# SCH_rocket_competetion_2025-11-04.net
KiCad netlist of a schematic drawn in EasyEDA
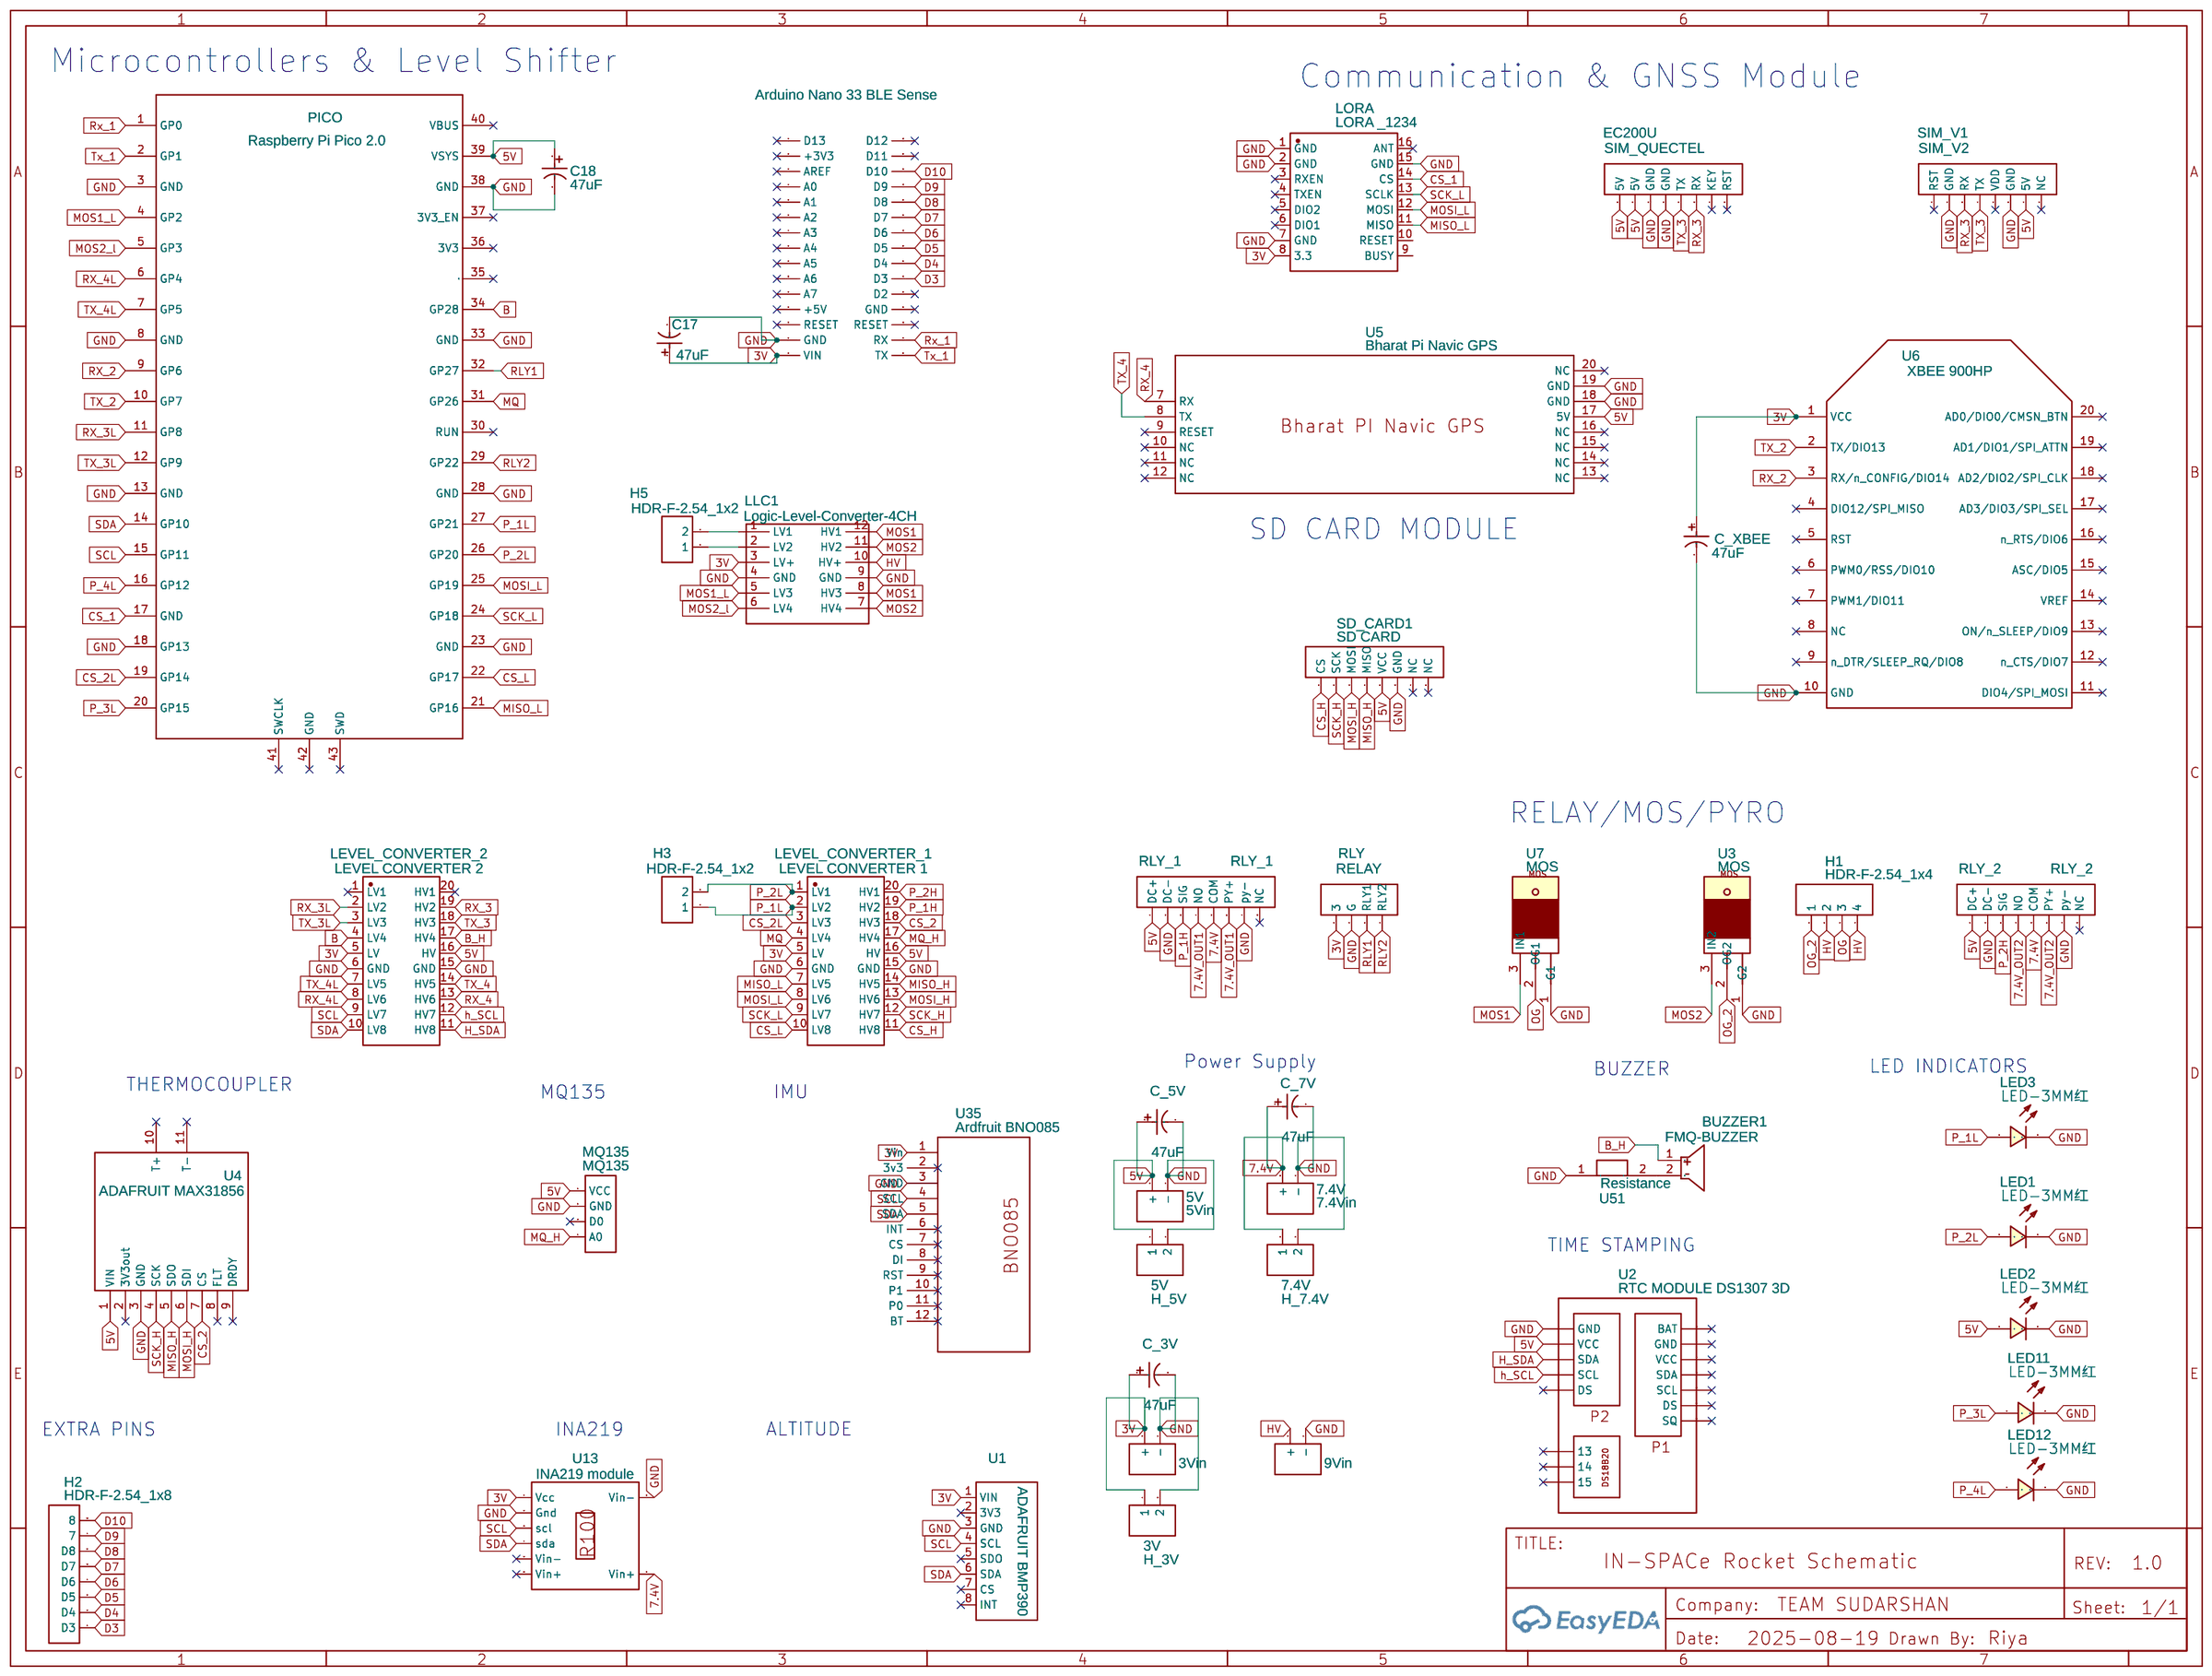
[diagram p0: schematic sheet]

(export (version "E")
  (design (tool "Eeschema 10.0.6"))
  (components
    (comp (ref "3.3V") (value "3Vin") (libsource (lib "") (part "CONN-TH_2P-P5.00")))
    (comp (ref "5V") (value "5Vin") (libsource (lib "") (part "CONN-TH_2P-P5.00_2")))
    (comp (ref "7.4V") (value "7.4Vin") (libsource (lib "") (part "CONN-TH_2P-P5.00_1")))
    (comp (ref "9V") (value "9Vin") (libsource (lib "") (part "CONN-TH_2P-P5.00_3")))
    (comp (ref "BLE33")
      (value "Arduino Nano 33 BLE Sense")
      (libsource (lib "") (part "Arduino Nano 33 BLE Sense"))
    )
    (comp (ref "BUZZER1")
      (value "FMQ-BUZZER")
      (fields (field (name "Manufacturer Part") "FMQ-BUZZER2"))
      (libsource (lib "") (part "FMQ-BUZZER2"))
    )
    (comp (ref "C17")
      (value "47uF")
      (fields
        (field (name "Manufacturer Part") "KM476M016D11RR0VH2FP0")
        (field (name "Manufacturer") "CX(承兴)")
      )
      (libsource (lib "") (part "CAPACITOR COPY_5"))
    )
    (comp (ref "C18")
      (value "47uF")
      (fields
        (field (name "Manufacturer Part") "KM476M016D11RR0VH2FP0")
        (field (name "Manufacturer") "CX(承兴)")
      )
      (libsource (lib "") (part "CAPACITOR COPY_1"))
    )
    (comp (ref "C_3V")
      (value "47uF")
      (fields
        (field (name "Manufacturer Part") "KM476M016D11RR0VH2FP0")
        (field (name "Manufacturer") "CX(承兴)")
      )
      (libsource (lib "") (part "CAPACITOR COPY_3"))
    )
    (comp (ref "C_5V")
      (value "47uF")
      (fields
        (field (name "Manufacturer Part") "KM476M016D11RR0VH2FP0")
        (field (name "Manufacturer") "CX(承兴)")
      )
      (libsource (lib "") (part "CAPACITOR COPY"))
    )
    (comp (ref "C_7V")
      (value "47uF")
      (fields
        (field (name "Manufacturer Part") "KM476M016D11RR0VH2FP0")
        (field (name "Manufacturer") "CX(承兴)")
      )
      (libsource (lib "") (part "CAPACITOR COPY_4"))
    )
    (comp (ref "C_XBEE")
      (value "47uF")
      (fields
        (field (name "Manufacturer Part") "KM476M016D11RR0VH2FP0")
        (field (name "Manufacturer") "CX(承兴)")
      )
      (libsource (lib "") (part "CAPACITOR COPY_2"))
    )
    (comp (ref "EC200U") (value "SIM_QUECTEL") (libsource (lib "") (part "HDR-F-2.54_1x8_3")))
    (comp (ref "H1") (value "HDR-F-2.54_1x4") (libsource (lib "") (part "HDR-F-2.54_1x4")))
    (comp (ref "H2") (value "HDR-F-2.54_1x8") (libsource (lib "") (part "HDR-F-2.54_1x8")))
    (comp (ref "H3") (value "HDR-F-2.54_1x2") (libsource (lib "") (part "HDR-F-2.54_1x2")))
    (comp (ref "H5") (value "HDR-F-2.54_1x2") (libsource (lib "") (part "HDR-F-2.54_1x2")))
    (comp (ref "H_3V") (value "3V") (libsource (lib "") (part "HDR-F-2.54_1x2_3")))
    (comp (ref "H_5V") (value "5V") (libsource (lib "") (part "HDR-F-2.54_1x2_2")))
    (comp (ref "H_7.4V") (value "7.4V") (libsource (lib "") (part "HDR-F-2.54_1x2_1")))
    (comp (ref "LED1")
      (value "LED-3MM红")
      (fields (field (name "Manufacturer Part") "LED-3mm红"))
      (libsource (lib "") (part "LED-3MM红"))
    )
    (comp (ref "LED2")
      (value "LED-3MM红")
      (fields (field (name "Manufacturer Part") "LED-3mm红"))
      (libsource (lib "") (part "LED-3MM红"))
    )
    (comp (ref "LED3")
      (value "LED-3MM红")
      (fields (field (name "Manufacturer Part") "LED-3mm红"))
      (libsource (lib "") (part "LED-3MM红"))
    )
    (comp (ref "LED11")
      (value "LED-3MM红")
      (fields (field (name "Manufacturer Part") "LED-3mm红"))
      (libsource (lib "") (part "LED-3MM红"))
    )
    (comp (ref "LED12")
      (value "LED-3MM红")
      (fields (field (name "Manufacturer Part") "LED-3mm红"))
      (libsource (lib "") (part "LED-3MM红"))
    )
    (comp (ref "LEVEL_CONVERTER_1")
      (value "LEVEL CONVERTER 1")
      (fields (field (name "Manufacturer Part") "Level Converter 8"))
      (libsource (lib "") (part "LEVEL CONVERTER 8"))
    )
    (comp (ref "LEVEL_CONVERTER_2")
      (value "LEVEL CONVERTER 2")
      (fields (field (name "Manufacturer Part") "Level Converter 8"))
      (libsource (lib "") (part "LEVEL CONVERTER 8"))
    )
    (comp (ref "LLC1")
      (value "Logic-Level-Converter-4CH")
      (libsource (lib "") (part "Logic-Level-Converter-4CH"))
    )
    (comp (ref "LORA")
      (value "LORA _1234")
      (fields (field (name "Manufacturer Part") "LORA"))
      (libsource (lib "") (part "LORA _1234"))
    )
    (comp (ref "MQ135") (value "MQ135") (libsource (lib "") (part "HDR-F-2.54_1x4_2")))
    (comp (ref "PICO")
      (value "Raspberry Pi Pico 2.0")
      (fields (field (name "Manufacturer Part") "Raspberry Pi Pico"))
      (libsource (lib "") (part "Raspberry Pi Pico 2.0"))
    )
    (comp (ref "RLY") (value "RELAY") (libsource (lib "") (part "HDR-F-2.54_1x4_1")))
    (comp (ref "RLY_1") (value "RLY_1") (libsource (lib "") (part "HDR-F-2.54_1x8_2")))
    (comp (ref "RLY_2") (value "RLY_2") (libsource (lib "") (part "HDR-F-2.54_1x8_2")))
    (comp (ref "SD_CARD1") (value "SD CARD") (libsource (lib "") (part "HDR-F-2.54_1x8_4")))
    (comp (ref "SIM_V1") (value "SIM_V2") (libsource (lib "") (part "HDR-F-2.54_1x8_1")))
    (comp (ref "U1")
      (value "ADAFRUIT BMP390")
      (fields (field (name "Manufacturer Part") "ADAFRUIT"))
      (libsource (lib "") (part "ADAFRUIT BMP390 COPY"))
    )
    (comp (ref "U2") (value "RTC MODULE DS1307 3D") (libsource (lib "") (part "RTC MODULE DS1307 3D")))
    (comp (ref "U3") (value "MOS") (libsource (lib "") (part "MOS")))
    (comp (ref "U4")
      (value "ADAFRUIT MAX31856")
      (fields (field (name "Manufacturer Part") "ADAFRUIT"))
      (libsource (lib "") (part "ADAFRUIT MAX31856"))
    )
    (comp (ref "U5") (value "Bharat Pi Navic GPS") (libsource (lib "") (part "Bharat Pi Navic GPS")))
    (comp (ref "U6")
      (value "XBEE 900HP")
      (fields
        (field (name "Manufacturer Part") "XBP24CZ7PITB003")
        (field (name "Manufacturer") "Digi International")
      )
      (libsource (lib "") (part "XBEE_THT"))
    )
    (comp (ref "U7") (value "MOS") (libsource (lib "") (part "MOS_1")))
    (comp (ref "U13")
      (value "INA219 module")
      (fields (field (name "Manufacturer Part") "INA219") (field (name "Manufacturer") "TI"))
      (libsource (lib "") (part "INA219 module"))
    )
    (comp (ref "U35")
      (value "Ardfruit BNO085")
      (fields (field (name "Manufacturer") "Ardfruit"))
      (libsource (lib "") (part "Ardfruit BNO085"))
    )
    (comp (ref "U51") (value "Resistance") (libsource (lib "") (part "Resistance")))
  )
  (nets
    (net (code "1") (name "3V") (class "Default")
      (node (ref "3.3V") (pin "2") (pinfunction "+_2") (pintype "unspecified"))
      (node (ref "BLE33") (pin "15") (pinfunction "VIN_15") (pintype "unspecified"))
      (node (ref "C17") (pin "1") (pinfunction "1_1") (pintype "unspecified"))
      (node (ref "C_3V") (pin "1") (pinfunction "1_1") (pintype "unspecified"))
      (node (ref "C_XBEE") (pin "1") (pinfunction "1_1") (pintype "unspecified"))
      (node (ref "H_3V") (pin "1") (pinfunction "1_1") (pintype "input"))
      (node (ref "LEVEL_CONVERTER_1") (pin "5") (pinfunction "LV_5") (pintype "unspecified"))
      (node (ref "LEVEL_CONVERTER_2") (pin "5") (pinfunction "LV_5") (pintype "unspecified"))
      (node (ref "LLC1") (pin "3") (pinfunction "LV+_3") (pintype "unspecified"))
      (node (ref "LORA") (pin "8") (pinfunction "3.3_8") (pintype "unspecified"))
      (node (ref "RLY") (pin "1") (pinfunction "3_1") (pintype "unspecified"))
      (node (ref "U1") (pin "1") (pinfunction "VIN_1") (pintype "unspecified"))
      (node (ref "U13") (pin "1") (pinfunction "Vcc_1") (pintype "input"))
      (node (ref "U35") (pin "1") (pinfunction "Vin_1") (pintype "unspecified"))
      (node (ref "U6") (pin "1") (pinfunction "VCC_1") (pintype "passive"))
    )
    (net (code "2") (name "5V") (class "Default")
      (node (ref "5V") (pin "2") (pinfunction "+_2") (pintype "unspecified"))
      (node (ref "C18") (pin "1") (pinfunction "1_1") (pintype "unspecified"))
      (node (ref "C_5V") (pin "1") (pinfunction "1_1") (pintype "unspecified"))
      (node (ref "EC200U") (pin "1") (pinfunction "5V_1") (pintype "unspecified"))
      (node (ref "EC200U") (pin "2") (pinfunction "5V_2") (pintype "unspecified"))
      (node (ref "H_5V") (pin "1") (pinfunction "1_1") (pintype "input"))
      (node (ref "LED2") (pin "1") (pinfunction "1_1") (pintype "unspecified"))
      (node (ref "LEVEL_CONVERTER_1") (pin "16") (pinfunction "HV_16") (pintype "unspecified"))
      (node (ref "LEVEL_CONVERTER_2") (pin "16") (pinfunction "HV_16") (pintype "unspecified"))
      (node (ref "MQ135") (pin "1") (pinfunction "VCC_1") (pintype "unspecified"))
      (node (ref "PICO") (pin "39") (pinfunction "VSYS_39") (pintype "unspecified"))
      (node (ref "RLY_1") (pin "1") (pinfunction "DC+_1") (pintype "unspecified"))
      (node (ref "RLY_2") (pin "1") (pinfunction "DC+_1") (pintype "unspecified"))
      (node (ref "SD_CARD1") (pin "5") (pinfunction "VCC_5") (pintype "unspecified"))
      (node (ref "SIM_V1") (pin "7") (pinfunction "5V_7") (pintype "unspecified"))
      (node (ref "U2") (pin "2") (pinfunction "VCC_2") (pintype "unspecified"))
      (node (ref "U4") (pin "1") (pinfunction "VIN_1") (pintype "unspecified"))
      (node (ref "U5") (pin "17") (pinfunction "5V_17") (pintype "unspecified"))
    )
    (net (code "3") (name "7.4V") (class "Default")
      (node (ref "7.4V") (pin "2") (pinfunction "+_2") (pintype "unspecified"))
      (node (ref "C_7V") (pin "1") (pinfunction "1_1") (pintype "unspecified"))
      (node (ref "H_7.4V") (pin "1") (pinfunction "1_1") (pintype "input"))
      (node (ref "RLY_1") (pin "5") (pinfunction "COM_5") (pintype "unspecified"))
      (node (ref "RLY_2") (pin "5") (pinfunction "COM_5") (pintype "unspecified"))
      (node (ref "U13") (pin "6") (pinfunction "Vin+_6") (pintype "input"))
    )
    (net (code "4") (name "7.4V_OUT1") (class "Default")
      (node (ref "RLY_1") (pin "4") (pinfunction "NO_4") (pintype "unspecified"))
      (node (ref "RLY_1") (pin "6") (pinfunction "PY+_6") (pintype "unspecified"))
    )
    (net (code "5") (name "7.4V_OUT2") (class "Default")
      (node (ref "RLY_2") (pin "4") (pinfunction "NO_4") (pintype "unspecified"))
      (node (ref "RLY_2") (pin "6") (pinfunction "PY+_6") (pintype "unspecified"))
    )
    (net (code "6") (name "B") (class "Default")
      (node (ref "LEVEL_CONVERTER_2") (pin "4") (pinfunction "LV4_4") (pintype "unspecified"))
      (node (ref "PICO") (pin "34") (pinfunction "GP28_34") (pintype "unspecified"))
    )
    (net (code "7") (name "B_H") (class "Default")
      (node (ref "BUZZER1") (pin "1") (pinfunction "1_1") (pintype "unspecified"))
      (node (ref "LEVEL_CONVERTER_2") (pin "17") (pinfunction "HV4_17") (pintype "unspecified"))
    )
    (net (code "8") (name "CS_1") (class "Default")
      (node (ref "LORA") (pin "14") (pinfunction "CS_14") (pintype "unspecified"))
      (node (ref "PICO") (pin "17") (pinfunction "GND_17") (pintype "unspecified"))
    )
    (net (code "9") (name "CS_2") (class "Default")
      (node (ref "LEVEL_CONVERTER_1") (pin "18") (pinfunction "HV3_18") (pintype "unspecified"))
      (node (ref "U4") (pin "7") (pinfunction "CS_7") (pintype "unspecified"))
    )
    (net (code "10") (name "CS_2L") (class "Default")
      (node (ref "LEVEL_CONVERTER_1") (pin "3") (pinfunction "LV3_3") (pintype "unspecified"))
      (node (ref "PICO") (pin "19") (pinfunction "GP14_19") (pintype "unspecified"))
    )
    (net (code "11") (name "CS_H") (class "Default")
      (node (ref "LEVEL_CONVERTER_1") (pin "11") (pinfunction "HV8_11") (pintype "unspecified"))
      (node (ref "SD_CARD1") (pin "1") (pinfunction "CS_1") (pintype "unspecified"))
    )
    (net (code "12") (name "CS_L") (class "Default")
      (node (ref "LEVEL_CONVERTER_1") (pin "10") (pinfunction "LV8_10") (pintype "unspecified"))
      (node (ref "PICO") (pin "22") (pinfunction "GP17_22") (pintype "unspecified"))
    )
    (net (code "13") (name "D3") (class "Default")
      (node (ref "BLE33") (pin "21") (pinfunction "D3_21") (pintype "unspecified"))
      (node (ref "H2") (pin "1") (pinfunction "D3_1") (pintype "unspecified"))
    )
    (net (code "14") (name "D4") (class "Default")
      (node (ref "BLE33") (pin "22") (pinfunction "D4_22") (pintype "unspecified"))
      (node (ref "H2") (pin "2") (pinfunction "D4_2") (pintype "unspecified"))
    )
    (net (code "15") (name "D5") (class "Default")
      (node (ref "BLE33") (pin "23") (pinfunction "D5_23") (pintype "unspecified"))
      (node (ref "H2") (pin "3") (pinfunction "D5_3") (pintype "unspecified"))
    )
    (net (code "16") (name "D6") (class "Default")
      (node (ref "BLE33") (pin "24") (pinfunction "D6_24") (pintype "unspecified"))
      (node (ref "H2") (pin "4") (pinfunction "D6_4") (pintype "unspecified"))
    )
    (net (code "17") (name "D7") (class "Default")
      (node (ref "BLE33") (pin "25") (pinfunction "D7_25") (pintype "unspecified"))
      (node (ref "H2") (pin "5") (pinfunction "D7_5") (pintype "unspecified"))
    )
    (net (code "18") (name "D8") (class "Default")
      (node (ref "BLE33") (pin "26") (pinfunction "D8_26") (pintype "unspecified"))
      (node (ref "H2") (pin "6") (pinfunction "D8_6") (pintype "unspecified"))
    )
    (net (code "19") (name "D9") (class "Default")
      (node (ref "BLE33") (pin "27") (pinfunction "D9_27") (pintype "unspecified"))
      (node (ref "H2") (pin "7") (pinfunction "7_7") (pintype "unspecified"))
    )
    (net (code "20") (name "D10") (class "Default")
      (node (ref "BLE33") (pin "28") (pinfunction "D10_28") (pintype "unspecified"))
      (node (ref "H2") (pin "8") (pinfunction "8_8") (pintype "unspecified"))
    )
    (net (code "21") (name "GND") (class "Default")
      (node (ref "3.3V") (pin "1") (pinfunction "-_1") (pintype "unspecified"))
      (node (ref "5V") (pin "1") (pinfunction "-_1") (pintype "unspecified"))
      (node (ref "7.4V") (pin "1") (pinfunction "-_1") (pintype "unspecified"))
      (node (ref "9V") (pin "1") (pinfunction "-_1") (pintype "unspecified"))
      (node (ref "BLE33") (pin "14") (pinfunction "GND_14") (pintype "unspecified"))
      (node (ref "C17") (pin "2") (pinfunction "2_2") (pintype "unspecified"))
      (node (ref "C18") (pin "2") (pinfunction "2_2") (pintype "unspecified"))
      (node (ref "C_3V") (pin "2") (pinfunction "2_2") (pintype "unspecified"))
      (node (ref "C_5V") (pin "2") (pinfunction "2_2") (pintype "unspecified"))
      (node (ref "C_7V") (pin "2") (pinfunction "2_2") (pintype "unspecified"))
      (node (ref "C_XBEE") (pin "2") (pinfunction "2_2") (pintype "unspecified"))
      (node (ref "EC200U") (pin "3") (pinfunction "GND_3") (pintype "unspecified"))
      (node (ref "EC200U") (pin "4") (pinfunction "GND_4") (pintype "unspecified"))
      (node (ref "H_3V") (pin "2") (pinfunction "2_2") (pintype "input"))
      (node (ref "H_5V") (pin "2") (pinfunction "2_2") (pintype "input"))
      (node (ref "H_7.4V") (pin "2") (pinfunction "2_2") (pintype "input"))
      (node (ref "LED1") (pin "2") (pinfunction "2_2") (pintype "unspecified"))
      (node (ref "LED11") (pin "2") (pinfunction "2_2") (pintype "unspecified"))
      (node (ref "LED12") (pin "2") (pinfunction "2_2") (pintype "unspecified"))
      (node (ref "LED2") (pin "2") (pinfunction "2_2") (pintype "unspecified"))
      (node (ref "LED3") (pin "2") (pinfunction "2_2") (pintype "unspecified"))
      (node (ref "LEVEL_CONVERTER_1") (pin "15") (pinfunction "GND_15") (pintype "unspecified"))
      (node (ref "LEVEL_CONVERTER_1") (pin "6") (pinfunction "GND_6") (pintype "unspecified"))
      (node (ref "LEVEL_CONVERTER_2") (pin "15") (pinfunction "GND_15") (pintype "unspecified"))
      (node (ref "LEVEL_CONVERTER_2") (pin "6") (pinfunction "GND_6") (pintype "unspecified"))
      (node (ref "LLC1") (pin "4") (pinfunction "GND_4") (pintype "unspecified"))
      (node (ref "LLC1") (pin "9") (pinfunction "GND_9") (pintype "unspecified"))
      (node (ref "LORA") (pin "1") (pinfunction "GND_1") (pintype "unspecified"))
      (node (ref "LORA") (pin "15") (pinfunction "GND_15") (pintype "unspecified"))
      (node (ref "LORA") (pin "2") (pinfunction "GND_2") (pintype "unspecified"))
      (node (ref "LORA") (pin "7") (pinfunction "GND_7") (pintype "unspecified"))
      (node (ref "MQ135") (pin "2") (pinfunction "GND_2") (pintype "unspecified"))
      (node (ref "PICO") (pin "13") (pinfunction "GND_13") (pintype "unspecified"))
      (node (ref "PICO") (pin "18") (pinfunction "GP13_18") (pintype "unspecified"))
      (node (ref "PICO") (pin "23") (pinfunction "GND_23") (pintype "unspecified"))
      (node (ref "PICO") (pin "28") (pinfunction "GND_28") (pintype "unspecified"))
      (node (ref "PICO") (pin "3") (pinfunction "GND_3") (pintype "unspecified"))
      (node (ref "PICO") (pin "33") (pinfunction "GND_33") (pintype "unspecified"))
      (node (ref "PICO") (pin "38") (pinfunction "GND_38") (pintype "unspecified"))
      (node (ref "PICO") (pin "8") (pinfunction "GND_8") (pintype "unspecified"))
      (node (ref "RLY") (pin "2") (pinfunction "G_2") (pintype "unspecified"))
      (node (ref "RLY_1") (pin "2") (pinfunction "DC-_2") (pintype "unspecified"))
      (node (ref "RLY_1") (pin "7") (pinfunction "py-_7") (pintype "unspecified"))
      (node (ref "RLY_2") (pin "2") (pinfunction "DC-_2") (pintype "unspecified"))
      (node (ref "RLY_2") (pin "7") (pinfunction "py-_7") (pintype "unspecified"))
      (node (ref "SD_CARD1") (pin "6") (pinfunction "GND_6") (pintype "unspecified"))
      (node (ref "SIM_V1") (pin "2") (pinfunction "GND_2") (pintype "unspecified"))
      (node (ref "SIM_V1") (pin "6") (pinfunction "GND_6") (pintype "unspecified"))
      (node (ref "U1") (pin "3") (pinfunction "GND_3") (pintype "unspecified"))
      (node (ref "U13") (pin "2") (pinfunction "Gnd_2") (pintype "input"))
      (node (ref "U13") (pin "5") (pinfunction "Vin-_5") (pintype "input"))
      (node (ref "U2") (pin "1") (pinfunction "GND_1") (pintype "unspecified"))
      (node (ref "U3") (pin "1") (pinfunction "G2_1") (pintype "unspecified"))
      (node (ref "U35") (pin "3") (pinfunction "GND_3") (pintype "unspecified"))
      (node (ref "U4") (pin "3") (pinfunction "GND_3") (pintype "unspecified"))
      (node (ref "U5") (pin "18") (pinfunction "GND_18") (pintype "unspecified"))
      (node (ref "U5") (pin "19") (pinfunction "GND_19") (pintype "unspecified"))
      (node (ref "U51") (pin "1") (pinfunction "1_1") (pintype "unspecified"))
      (node (ref "U6") (pin "10") (pinfunction "GND_10") (pintype "passive"))
      (node (ref "U7") (pin "1") (pinfunction "G1_1") (pintype "unspecified"))
    )
    (net (code "22") (name "HV") (class "Default")
      (node (ref "9V") (pin "2") (pinfunction "+_2") (pintype "unspecified"))
      (node (ref "H1") (pin "2") (pinfunction "2_2") (pintype "unspecified"))
      (node (ref "H1") (pin "4") (pinfunction "4_4") (pintype "unspecified"))
      (node (ref "LLC1") (pin "10") (pinfunction "HV+_10") (pintype "unspecified"))
    )
    (net (code "23") (name "H_SDA") (class "Default")
      (node (ref "LEVEL_CONVERTER_2") (pin "11") (pinfunction "HV8_11") (pintype "unspecified"))
      (node (ref "U2") (pin "3") (pinfunction "SDA_3") (pintype "unspecified"))
    )
    (net (code "24") (name "MISO_H") (class "Default")
      (node (ref "LEVEL_CONVERTER_1") (pin "14") (pinfunction "HV5_14") (pintype "unspecified"))
      (node (ref "SD_CARD1") (pin "4") (pinfunction "MISO_4") (pintype "unspecified"))
      (node (ref "U4") (pin "5") (pinfunction "SDO_5") (pintype "unspecified"))
    )
    (net (code "25") (name "MISO_L") (class "Default")
      (node (ref "LEVEL_CONVERTER_1") (pin "7") (pinfunction "LV5_7") (pintype "unspecified"))
      (node (ref "LORA") (pin "11") (pinfunction "MISO_11") (pintype "unspecified"))
      (node (ref "PICO") (pin "21") (pinfunction "GP16_21") (pintype "unspecified"))
    )
    (net (code "26") (name "MOS1") (class "Default")
      (node (ref "LLC1") (pin "12") (pinfunction "HV1_12") (pintype "unspecified"))
      (node (ref "LLC1") (pin "8") (pinfunction "HV3_8") (pintype "unspecified"))
      (node (ref "U7") (pin "3") (pinfunction "IN1_3") (pintype "unspecified"))
    )
    (net (code "27") (name "MOS1_L") (class "Default")
      (node (ref "LLC1") (pin "5") (pinfunction "LV3_5") (pintype "unspecified"))
      (node (ref "PICO") (pin "4") (pinfunction "GP2_4") (pintype "unspecified"))
    )
    (net (code "28") (name "MOS2") (class "Default")
      (node (ref "LLC1") (pin "11") (pinfunction "HV2_11") (pintype "unspecified"))
      (node (ref "LLC1") (pin "7") (pinfunction "HV4_7") (pintype "unspecified"))
      (node (ref "U3") (pin "3") (pinfunction "IN2_3") (pintype "unspecified"))
    )
    (net (code "29") (name "MOS2_l") (class "Default")
      (node (ref "LLC1") (pin "6") (pinfunction "LV4_6") (pintype "unspecified"))
      (node (ref "PICO") (pin "5") (pinfunction "GP3_5") (pintype "unspecified"))
    )
    (net (code "30") (name "MOSI_H") (class "Default")
      (node (ref "LEVEL_CONVERTER_1") (pin "13") (pinfunction "HV6_13") (pintype "unspecified"))
      (node (ref "SD_CARD1") (pin "3") (pinfunction "MOSI_3") (pintype "unspecified"))
      (node (ref "U4") (pin "6") (pinfunction "SDI_6") (pintype "unspecified"))
    )
    (net (code "31") (name "MOSI_L") (class "Default")
      (node (ref "LEVEL_CONVERTER_1") (pin "8") (pinfunction "LV6_8") (pintype "unspecified"))
      (node (ref "LORA") (pin "12") (pinfunction "MOSI_12") (pintype "unspecified"))
      (node (ref "PICO") (pin "25") (pinfunction "GP19_25") (pintype "unspecified"))
    )
    (net (code "32") (name "MQ") (class "Default")
      (node (ref "LEVEL_CONVERTER_1") (pin "4") (pinfunction "LV4_4") (pintype "unspecified"))
      (node (ref "PICO") (pin "31") (pinfunction "GP26_31") (pintype "unspecified"))
    )
    (net (code "33") (name "MQ_H") (class "Default")
      (node (ref "LEVEL_CONVERTER_1") (pin "17") (pinfunction "HV4_17") (pintype "unspecified"))
      (node (ref "MQ135") (pin "4") (pinfunction "A0_4") (pintype "unspecified"))
    )
    (net (code "34") (name "Net-(BUZZER1-Pad2)") (class "Default")
      (node (ref "BUZZER1") (pin "2") (pinfunction "2_2") (pintype "unspecified"))
      (node (ref "U51") (pin "2") (pinfunction "2_2") (pintype "unspecified"))
    )
    (net (code "35") (name "Net-(LLC1-LV1)") (class "Default")
      (node (ref "H5") (pin "2") (pinfunction "2_2") (pintype "input"))
      (node (ref "LLC1") (pin "1") (pinfunction "LV1_1") (pintype "unspecified"))
    )
    (net (code "36") (name "Net-(LLC1-LV2)") (class "Default")
      (node (ref "H5") (pin "1") (pinfunction "1_1") (pintype "input"))
      (node (ref "LLC1") (pin "2") (pinfunction "LV2_2") (pintype "unspecified"))
    )
    (net (code "37") (name "OG") (class "Default")
      (node (ref "H1") (pin "3") (pinfunction "3_3") (pintype "unspecified"))
      (node (ref "U7") (pin "2") (pinfunction "OG1_2") (pintype "unspecified"))
    )
    (net (code "38") (name "OG_2") (class "Default")
      (node (ref "H1") (pin "1") (pinfunction "1_1") (pintype "unspecified"))
      (node (ref "U3") (pin "2") (pinfunction "OG2_2") (pintype "unspecified"))
    )
    (net (code "39") (name "P_1H") (class "Default")
      (node (ref "LEVEL_CONVERTER_1") (pin "19") (pinfunction "HV2_19") (pintype "unspecified"))
      (node (ref "RLY_1") (pin "3") (pinfunction "SIG_3") (pintype "unspecified"))
    )
    (net (code "40") (name "P_1L") (class "Default")
      (node (ref "H3") (pin "1") (pinfunction "1_1") (pintype "input"))
      (node (ref "LED3") (pin "1") (pinfunction "1_1") (pintype "unspecified"))
      (node (ref "LEVEL_CONVERTER_1") (pin "2") (pinfunction "LV2_2") (pintype "unspecified"))
      (node (ref "PICO") (pin "27") (pinfunction "GP21_27") (pintype "unspecified"))
    )
    (net (code "41") (name "P_2H") (class "Default")
      (node (ref "LEVEL_CONVERTER_1") (pin "20") (pinfunction "HV1_20") (pintype "unspecified"))
      (node (ref "RLY_2") (pin "3") (pinfunction "SIG_3") (pintype "unspecified"))
    )
    (net (code "42") (name "P_2L") (class "Default")
      (node (ref "H3") (pin "2") (pinfunction "2_2") (pintype "input"))
      (node (ref "LED1") (pin "1") (pinfunction "1_1") (pintype "unspecified"))
      (node (ref "LEVEL_CONVERTER_1") (pin "1") (pinfunction "LV1_1") (pintype "unspecified"))
      (node (ref "PICO") (pin "26") (pinfunction "GP20_26") (pintype "unspecified"))
    )
    (net (code "43") (name "P_3L") (class "Default")
      (node (ref "LED11") (pin "1") (pinfunction "1_1") (pintype "unspecified"))
      (node (ref "PICO") (pin "20") (pinfunction "GP15_20") (pintype "unspecified"))
    )
    (net (code "44") (name "P_4L") (class "Default")
      (node (ref "LED12") (pin "1") (pinfunction "1_1") (pintype "unspecified"))
      (node (ref "PICO") (pin "16") (pinfunction "GP12_16") (pintype "unspecified"))
    )
    (net (code "45") (name "RLY1") (class "Default")
      (node (ref "PICO") (pin "32") (pinfunction "GP27_32") (pintype "unspecified"))
      (node (ref "RLY") (pin "3") (pinfunction "RLY1_3") (pintype "unspecified"))
    )
    (net (code "46") (name "RLY2") (class "Default")
      (node (ref "PICO") (pin "29") (pinfunction "GP22_29") (pintype "unspecified"))
      (node (ref "RLY") (pin "4") (pinfunction "RLY2_4") (pintype "unspecified"))
    )
    (net (code "47") (name "RX_2") (class "Default")
      (node (ref "PICO") (pin "9") (pinfunction "GP6_9") (pintype "unspecified"))
      (node (ref "U6") (pin "3") (pinfunction "RX/n_CONFIG/DIO14_3") (pintype "input"))
    )
    (net (code "48") (name "RX_3") (class "Default")
      (node (ref "EC200U") (pin "6") (pinfunction "RX_6") (pintype "unspecified"))
      (node (ref "LEVEL_CONVERTER_2") (pin "19") (pinfunction "HV2_19") (pintype "unspecified"))
      (node (ref "SIM_V1") (pin "3") (pinfunction "RX_3") (pintype "unspecified"))
    )
    (net (code "49") (name "RX_3L") (class "Default")
      (node (ref "LEVEL_CONVERTER_2") (pin "2") (pinfunction "LV2_2") (pintype "unspecified"))
      (node (ref "PICO") (pin "11") (pinfunction "GP8_11") (pintype "unspecified"))
    )
    (net (code "50") (name "RX_4") (class "Default")
      (node (ref "LEVEL_CONVERTER_2") (pin "13") (pinfunction "HV6_13") (pintype "unspecified"))
      (node (ref "U5") (pin "7") (pinfunction "RX_7") (pintype "unspecified"))
    )
    (net (code "51") (name "RX_4L") (class "Default")
      (node (ref "LEVEL_CONVERTER_2") (pin "8") (pinfunction "LV6_8") (pintype "unspecified"))
      (node (ref "PICO") (pin "6") (pinfunction "GP4_6") (pintype "unspecified"))
    )
    (net (code "52") (name "Rx_1") (class "Default")
      (node (ref "BLE33") (pin "17") (pinfunction "RX_17") (pintype "unspecified"))
      (node (ref "PICO") (pin "1") (pinfunction "GP0_1") (pintype "unspecified"))
    )
    (net (code "53") (name "SCK_H") (class "Default")
      (node (ref "LEVEL_CONVERTER_1") (pin "12") (pinfunction "HV7_12") (pintype "unspecified"))
      (node (ref "SD_CARD1") (pin "2") (pinfunction "SCK_2") (pintype "unspecified"))
      (node (ref "U4") (pin "4") (pinfunction "SCK_4") (pintype "unspecified"))
    )
    (net (code "54") (name "SCK_L") (class "Default")
      (node (ref "LEVEL_CONVERTER_1") (pin "9") (pinfunction "LV7_9") (pintype "unspecified"))
      (node (ref "LORA") (pin "13") (pinfunction "SCLK_13") (pintype "unspecified"))
      (node (ref "PICO") (pin "24") (pinfunction "GP18_24") (pintype "unspecified"))
    )
    (net (code "55") (name "SCL") (class "Default")
      (node (ref "LEVEL_CONVERTER_2") (pin "9") (pinfunction "LV7_9") (pintype "unspecified"))
      (node (ref "PICO") (pin "15") (pinfunction "GP11_15") (pintype "unspecified"))
      (node (ref "U1") (pin "4") (pinfunction "SCL_4") (pintype "unspecified"))
      (node (ref "U13") (pin "3") (pinfunction "scl_3") (pintype "input"))
      (node (ref "U35") (pin "4") (pinfunction "SCL_4") (pintype "unspecified"))
    )
    (net (code "56") (name "SDA") (class "Default")
      (node (ref "LEVEL_CONVERTER_2") (pin "10") (pinfunction "LV8_10") (pintype "unspecified"))
      (node (ref "PICO") (pin "14") (pinfunction "GP10_14") (pintype "unspecified"))
      (node (ref "U1") (pin "6") (pinfunction "SDA_6") (pintype "unspecified"))
      (node (ref "U13") (pin "4") (pinfunction "sda_4") (pintype "input"))
      (node (ref "U35") (pin "5") (pinfunction "SDA_5") (pintype "unspecified"))
    )
    (net (code "57") (name "TX_2") (class "Default")
      (node (ref "PICO") (pin "10") (pinfunction "GP7_10") (pintype "unspecified"))
      (node (ref "U6") (pin "2") (pinfunction "TX/DIO13_2") (pintype "output"))
    )
    (net (code "58") (name "TX_3") (class "Default")
      (node (ref "EC200U") (pin "5") (pinfunction "TX_5") (pintype "unspecified"))
      (node (ref "LEVEL_CONVERTER_2") (pin "18") (pinfunction "HV3_18") (pintype "unspecified"))
      (node (ref "SIM_V1") (pin "4") (pinfunction "TX_4") (pintype "unspecified"))
    )
    (net (code "59") (name "TX_3L") (class "Default")
      (node (ref "LEVEL_CONVERTER_2") (pin "3") (pinfunction "LV3_3") (pintype "unspecified"))
      (node (ref "PICO") (pin "12") (pinfunction "GP9_12") (pintype "unspecified"))
    )
    (net (code "60") (name "TX_4") (class "Default")
      (node (ref "LEVEL_CONVERTER_2") (pin "14") (pinfunction "HV5_14") (pintype "unspecified"))
      (node (ref "U5") (pin "8") (pinfunction "TX_8") (pintype "unspecified"))
    )
    (net (code "61") (name "TX_4L") (class "Default")
      (node (ref "LEVEL_CONVERTER_2") (pin "7") (pinfunction "LV5_7") (pintype "unspecified"))
      (node (ref "PICO") (pin "7") (pinfunction "GP5_7") (pintype "unspecified"))
    )
    (net (code "62") (name "Tx_1") (class "Default")
      (node (ref "BLE33") (pin "16") (pinfunction "TX_16") (pintype "unspecified"))
      (node (ref "PICO") (pin "2") (pinfunction "GP1_2") (pintype "unspecified"))
    )
    (net (code "63") (name "h_SCL") (class "Default")
      (node (ref "LEVEL_CONVERTER_2") (pin "12") (pinfunction "HV7_12") (pintype "unspecified"))
      (node (ref "U2") (pin "4") (pinfunction "SCL_4") (pintype "unspecified"))
    )
    (net (code "64") (name "unconnected-(BLE33-+3V3-Pad2)") (class "Default")
      (node (ref "BLE33") (pin "2") (pinfunction "+3V3_2") (pintype "unspecified+no_connect"))
    )
    (net (code "65") (name "unconnected-(BLE33-+5V-Pad12)") (class "Default")
      (node (ref "BLE33") (pin "12") (pinfunction "+5V_12") (pintype "unspecified+no_connect"))
    )
    (net (code "66") (name "unconnected-(BLE33-A0-Pad4)") (class "Default")
      (node (ref "BLE33") (pin "4") (pinfunction "A0_4") (pintype "unspecified+no_connect"))
    )
    (net (code "67") (name "unconnected-(BLE33-A1-Pad5)") (class "Default")
      (node (ref "BLE33") (pin "5") (pinfunction "A1_5") (pintype "unspecified+no_connect"))
    )
    (net (code "68") (name "unconnected-(BLE33-A2-Pad6)") (class "Default")
      (node (ref "BLE33") (pin "6") (pinfunction "A2_6") (pintype "unspecified+no_connect"))
    )
    (net (code "69") (name "unconnected-(BLE33-A3-Pad7)") (class "Default")
      (node (ref "BLE33") (pin "7") (pinfunction "A3_7") (pintype "unspecified+no_connect"))
    )
    (net (code "70") (name "unconnected-(BLE33-A4-Pad8)") (class "Default")
      (node (ref "BLE33") (pin "8") (pinfunction "A4_8") (pintype "unspecified+no_connect"))
    )
    (net (code "71") (name "unconnected-(BLE33-A5-Pad9)") (class "Default")
      (node (ref "BLE33") (pin "9") (pinfunction "A5_9") (pintype "unspecified+no_connect"))
    )
    (net (code "72") (name "unconnected-(BLE33-A6-Pad10)") (class "Default")
      (node (ref "BLE33") (pin "10") (pinfunction "A6_10") (pintype "unspecified+no_connect"))
    )
    (net (code "73") (name "unconnected-(BLE33-A7-Pad11)") (class "Default")
      (node (ref "BLE33") (pin "11") (pinfunction "A7_11") (pintype "unspecified+no_connect"))
    )
    (net (code "74") (name "unconnected-(BLE33-AREF-Pad3)") (class "Default")
      (node (ref "BLE33") (pin "3") (pinfunction "AREF_3") (pintype "unspecified+no_connect"))
    )
    (net (code "75") (name "unconnected-(BLE33-D2-Pad20)") (class "Default")
      (node (ref "BLE33") (pin "20") (pinfunction "D2_20") (pintype "unspecified+no_connect"))
    )
    (net (code "76") (name "unconnected-(BLE33-D11-Pad29)") (class "Default")
      (node (ref "BLE33") (pin "29") (pinfunction "D11_29") (pintype "unspecified+no_connect"))
    )
    (net (code "77") (name "unconnected-(BLE33-D12-Pad30)") (class "Default")
      (node (ref "BLE33") (pin "30") (pinfunction "D12_30") (pintype "unspecified+no_connect"))
    )
    (net (code "78") (name "unconnected-(BLE33-D13-Pad1)") (class "Default")
      (node (ref "BLE33") (pin "1") (pinfunction "D13_1") (pintype "unspecified+no_connect"))
    )
    (net (code "79") (name "unconnected-(BLE33-GND-Pad19)") (class "Default")
      (node (ref "BLE33") (pin "19") (pinfunction "GND_19") (pintype "unspecified+no_connect"))
    )
    (net (code "80") (name "unconnected-(BLE33-RESET-Pad13)") (class "Default")
      (node (ref "BLE33") (pin "13") (pinfunction "RESET_13") (pintype "unspecified+no_connect"))
    )
    (net (code "81") (name "unconnected-(BLE33-RESET-Pad18)") (class "Default")
      (node (ref "BLE33") (pin "18") (pinfunction "RESET_18") (pintype "unspecified+no_connect"))
    )
    (net (code "82") (name "unconnected-(EC200U-KEY-Pad7)") (class "Default")
      (node (ref "EC200U") (pin "7") (pinfunction "KEY_7") (pintype "unspecified+no_connect"))
    )
    (net (code "83") (name "unconnected-(EC200U-RST-Pad8)") (class "Default")
      (node (ref "EC200U") (pin "8") (pinfunction "RST_8") (pintype "unspecified+no_connect"))
    )
    (net (code "84") (name "unconnected-(LEVEL_CONVERTER_2-HV1-Pad20)") (class "Default")
      (node (ref "LEVEL_CONVERTER_2") (pin "20") (pinfunction "HV1_20") (pintype "unspecified+no_connect"))
    )
    (net (code "85") (name "unconnected-(LEVEL_CONVERTER_2-LV1-Pad1)") (class "Default")
      (node (ref "LEVEL_CONVERTER_2") (pin "1") (pinfunction "LV1_1") (pintype "unspecified+no_connect"))
    )
    (net (code "86") (name "unconnected-(LORA-ANT-Pad16)") (class "Default")
      (node (ref "LORA") (pin "16") (pinfunction "ANT_16") (pintype "unspecified+no_connect"))
    )
    (net (code "87") (name "unconnected-(LORA-BUSY-Pad9)") (class "Default")
      (node (ref "LORA") (pin "9") (pinfunction "BUSY_9") (pintype "unspecified"))
    )
    (net (code "88") (name "unconnected-(LORA-DIO1-Pad6)") (class "Default")
      (node (ref "LORA") (pin "6") (pinfunction "DIO1_6") (pintype "unspecified+no_connect"))
    )
    (net (code "89") (name "unconnected-(LORA-DIO2-Pad5)") (class "Default")
      (node (ref "LORA") (pin "5") (pinfunction "DIO2_5") (pintype "unspecified+no_connect"))
    )
    (net (code "90") (name "unconnected-(LORA-RESET-Pad10)") (class "Default")
      (node (ref "LORA") (pin "10") (pinfunction "RESET_10") (pintype "unspecified"))
    )
    (net (code "91") (name "unconnected-(LORA-RXEN-Pad3)") (class "Default")
      (node (ref "LORA") (pin "3") (pinfunction "RXEN_3") (pintype "unspecified+no_connect"))
    )
    (net (code "92") (name "unconnected-(LORA-TXEN-Pad4)") (class "Default")
      (node (ref "LORA") (pin "4") (pinfunction "TXEN_4") (pintype "unspecified+no_connect"))
    )
    (net (code "93") (name "unconnected-(MQ135-D0-Pad3)") (class "Default")
      (node (ref "MQ135") (pin "3") (pinfunction "D0_3") (pintype "unspecified+no_connect"))
    )
    (net (code "94") (name "unconnected-(PICO-3V3-Pad36)") (class "Default")
      (node (ref "PICO") (pin "36") (pinfunction "3V3_36") (pintype "unspecified+no_connect"))
    )
    (net (code "95") (name "unconnected-(PICO-3V3_EN-Pad37)") (class "Default")
      (node (ref "PICO") (pin "37") (pinfunction "3V3_EN_37") (pintype "unspecified+no_connect"))
    )
    (net (code "96") (name "unconnected-(PICO-GND-Pad42)") (class "Default")
      (node (ref "PICO") (pin "42") (pinfunction "GND_42") (pintype "unspecified+no_connect"))
    )
    (net (code "97") (name "unconnected-(PICO-Pad35)") (class "Default")
      (node (ref "PICO") (pin "35") (pinfunction "35_35") (pintype "unspecified+no_connect"))
    )
    (net (code "98") (name "unconnected-(PICO-RUN-Pad30)") (class "Default")
      (node (ref "PICO") (pin "30") (pinfunction "RUN_30") (pintype "unspecified+no_connect"))
    )
    (net (code "99") (name "unconnected-(PICO-SWCLK-Pad41)") (class "Default")
      (node (ref "PICO") (pin "41") (pinfunction "SWCLK_41") (pintype "unspecified+no_connect"))
    )
    (net (code "100") (name "unconnected-(PICO-SWD-Pad43)") (class "Default")
      (node (ref "PICO") (pin "43") (pinfunction "SWD_43") (pintype "unspecified+no_connect"))
    )
    (net (code "101") (name "unconnected-(PICO-VBUS-Pad40)") (class "Default")
      (node (ref "PICO") (pin "40") (pinfunction "VBUS_40") (pintype "unspecified+no_connect"))
    )
    (net (code "102") (name "unconnected-(RLY_1-NC-Pad8)") (class "Default")
      (node (ref "RLY_1") (pin "8") (pinfunction "NC_8") (pintype "unspecified+no_connect"))
    )
    (net (code "103") (name "unconnected-(RLY_2-NC-Pad8)") (class "Default")
      (node (ref "RLY_2") (pin "8") (pinfunction "NC_8") (pintype "unspecified+no_connect"))
    )
    (net (code "104") (name "unconnected-(SD_CARD1-NC-Pad7)") (class "Default")
      (node (ref "SD_CARD1") (pin "7") (pinfunction "NC_7") (pintype "unspecified+no_connect"))
    )
    (net (code "105") (name "unconnected-(SD_CARD1-NC-Pad8)") (class "Default")
      (node (ref "SD_CARD1") (pin "8") (pinfunction "NC_8") (pintype "unspecified+no_connect"))
    )
    (net (code "106") (name "unconnected-(SIM_V1-NC-Pad8)") (class "Default")
      (node (ref "SIM_V1") (pin "8") (pinfunction "NC_8") (pintype "unspecified+no_connect"))
    )
    (net (code "107") (name "unconnected-(SIM_V1-RST-Pad1)") (class "Default")
      (node (ref "SIM_V1") (pin "1") (pinfunction "RST_1") (pintype "unspecified+no_connect"))
    )
    (net (code "108") (name "unconnected-(SIM_V1-VDD-Pad5)") (class "Default")
      (node (ref "SIM_V1") (pin "5") (pinfunction "VDD_5") (pintype "unspecified+no_connect"))
    )
    (net (code "109") (name "unconnected-(U1-3V3-Pad2)") (class "Default")
      (node (ref "U1") (pin "2") (pinfunction "3V3_2") (pintype "unspecified+no_connect"))
    )
    (net (code "110") (name "unconnected-(U1-CS-Pad7)") (class "Default")
      (node (ref "U1") (pin "7") (pinfunction "CS_7") (pintype "unspecified+no_connect"))
    )
    (net (code "111") (name "unconnected-(U1-INT-Pad8)") (class "Default")
      (node (ref "U1") (pin "8") (pinfunction "INT_8") (pintype "unspecified+no_connect"))
    )
    (net (code "112") (name "unconnected-(U1-SDO-Pad5)") (class "Default")
      (node (ref "U1") (pin "5") (pinfunction "SDO_5") (pintype "unspecified+no_connect"))
    )
    (net (code "113") (name "unconnected-(U2-BAT-Pad6)") (class "Default")
      (node (ref "U2") (pin "6") (pinfunction "BAT_6") (pintype "unspecified+no_connect"))
    )
    (net (code "114") (name "unconnected-(U2-DS-Pad5)") (class "Default")
      (node (ref "U2") (pin "5") (pinfunction "DS_5") (pintype "unspecified+no_connect"))
    )
    (net (code "115") (name "unconnected-(U2-DS-Pad11)") (class "Default")
      (node (ref "U2") (pin "11") (pinfunction "DS_11") (pintype "unspecified+no_connect"))
    )
    (net (code "116") (name "unconnected-(U2-GND-Pad7)") (class "Default")
      (node (ref "U2") (pin "7") (pinfunction "GND_7") (pintype "unspecified+no_connect"))
    )
    (net (code "117") (name "unconnected-(U2-Pad13)") (class "Default")
      (node (ref "U2") (pin "13") (pinfunction "13_13") (pintype "unspecified+no_connect"))
    )
    (net (code "118") (name "unconnected-(U2-Pad14)") (class "Default")
      (node (ref "U2") (pin "14") (pinfunction "14_14") (pintype "unspecified+no_connect"))
    )
    (net (code "119") (name "unconnected-(U2-Pad15)") (class "Default")
      (node (ref "U2") (pin "15") (pinfunction "15_15") (pintype "unspecified+no_connect"))
    )
    (net (code "120") (name "unconnected-(U2-SCL-Pad10)") (class "Default")
      (node (ref "U2") (pin "10") (pinfunction "SCL_10") (pintype "unspecified+no_connect"))
    )
    (net (code "121") (name "unconnected-(U2-SDA-Pad9)") (class "Default")
      (node (ref "U2") (pin "9") (pinfunction "SDA_9") (pintype "unspecified+no_connect"))
    )
    (net (code "122") (name "unconnected-(U2-SQ-Pad12)") (class "Default")
      (node (ref "U2") (pin "12") (pinfunction "SQ_12") (pintype "unspecified+no_connect"))
    )
    (net (code "123") (name "unconnected-(U2-VCC-Pad8)") (class "Default")
      (node (ref "U2") (pin "8") (pinfunction "VCC_8") (pintype "unspecified+no_connect"))
    )
    (net (code "124") (name "unconnected-(U4-3V3out-Pad2)") (class "Default")
      (node (ref "U4") (pin "2") (pinfunction "3V3out_2") (pintype "unspecified+no_connect"))
    )
    (net (code "125") (name "unconnected-(U4-DRDY-Pad9)") (class "Default")
      (node (ref "U4") (pin "9") (pinfunction "DRDY_9") (pintype "unspecified+no_connect"))
    )
    (net (code "126") (name "unconnected-(U4-FLT-Pad8)") (class "Default")
      (node (ref "U4") (pin "8") (pinfunction "FLT_8") (pintype "unspecified+no_connect"))
    )
    (net (code "127") (name "unconnected-(U4-T+-Pad10)") (class "Default")
      (node (ref "U4") (pin "10") (pinfunction "T+_10") (pintype "unspecified+no_connect"))
    )
    (net (code "128") (name "unconnected-(U4-T--Pad11)") (class "Default")
      (node (ref "U4") (pin "11") (pinfunction "T-_11") (pintype "unspecified+no_connect"))
    )
    (net (code "129") (name "unconnected-(U5-NC-Pad10)") (class "Default")
      (node (ref "U5") (pin "10") (pinfunction "NC_10") (pintype "unspecified+no_connect"))
    )
    (net (code "130") (name "unconnected-(U5-NC-Pad11)") (class "Default")
      (node (ref "U5") (pin "11") (pinfunction "NC_11") (pintype "unspecified+no_connect"))
    )
    (net (code "131") (name "unconnected-(U5-NC-Pad12)") (class "Default")
      (node (ref "U5") (pin "12") (pinfunction "NC_12") (pintype "unspecified+no_connect"))
    )
    (net (code "132") (name "unconnected-(U5-NC-Pad13)") (class "Default")
      (node (ref "U5") (pin "13") (pinfunction "NC_13") (pintype "unspecified+no_connect"))
    )
    (net (code "133") (name "unconnected-(U5-NC-Pad14)") (class "Default")
      (node (ref "U5") (pin "14") (pinfunction "NC_14") (pintype "unspecified+no_connect"))
    )
    (net (code "134") (name "unconnected-(U5-NC-Pad15)") (class "Default")
      (node (ref "U5") (pin "15") (pinfunction "NC_15") (pintype "unspecified+no_connect"))
    )
    (net (code "135") (name "unconnected-(U5-NC-Pad16)") (class "Default")
      (node (ref "U5") (pin "16") (pinfunction "NC_16") (pintype "unspecified+no_connect"))
    )
    (net (code "136") (name "unconnected-(U5-NC-Pad20)") (class "Default")
      (node (ref "U5") (pin "20") (pinfunction "NC_20") (pintype "unspecified+no_connect"))
    )
    (net (code "137") (name "unconnected-(U5-RESET-Pad9)") (class "Default")
      (node (ref "U5") (pin "9") (pinfunction "RESET_9") (pintype "unspecified+no_connect"))
    )
    (net (code "138") (name "unconnected-(U6-AD0{slash}DIO0{slash}CMSN_BTN-Pad20)") (class "Default")
      (node (ref "U6") (pin "20") (pinfunction "AD0/DIO0/CMSN_BTN_20") (pintype "input+no_connect"))
    )
    (net (code "139") (name "unconnected-(U6-AD1{slash}DIO1{slash}SPI_ATTN-Pad19)") (class "Default")
      (node (ref "U6") (pin "19") (pinfunction "AD1/DIO1/SPI_ATTN_19") (pintype "bidirectional+no_connect"))
    )
    (net (code "140") (name "unconnected-(U6-AD2{slash}DIO2{slash}SPI_CLK-Pad18)") (class "Default")
      (node (ref "U6") (pin "18") (pinfunction "AD2/DIO2/SPI_CLK_18") (pintype "bidirectional+no_connect"))
    )
    (net (code "141") (name "unconnected-(U6-AD3{slash}DIO3{slash}SPI_SEL-Pad17)") (class "Default")
      (node (ref "U6") (pin "17") (pinfunction "AD3/DIO3/SPI_SEL_17") (pintype "bidirectional+no_connect"))
    )
    (net (code "142") (name "unconnected-(U6-ASC{slash}DIO5-Pad15)") (class "Default")
      (node (ref "U6") (pin "15") (pinfunction "ASC/DIO5_15") (pintype "input+no_connect"))
    )
    (net (code "143") (name "unconnected-(U6-DIO4{slash}SPI_MOSI-Pad11)") (class "Default")
      (node (ref "U6") (pin "11") (pinfunction "DIO4/SPI_MOSI_11") (pintype "input+no_connect"))
    )
    (net (code "144") (name "unconnected-(U6-DIO12{slash}SPI_MISO-Pad4)") (class "Default")
      (node (ref "U6") (pin "4") (pinfunction "DIO12/SPI_MISO_4") (pintype "bidirectional+no_connect"))
    )
    (net (code "145") (name "unconnected-(U6-NC-Pad8)") (class "Default")
      (node (ref "U6") (pin "8") (pinfunction "NC_8") (pintype "input+no_connect"))
    )
    (net (code "146") (name "unconnected-(U6-ON{slash}n_SLEEP{slash}DIO9-Pad13)") (class "Default")
      (node (ref "U6") (pin "13") (pinfunction "ON/n_SLEEP/DIO9_13") (pintype "bidirectional+no_connect"))
    )
    (net (code "147") (name "unconnected-(U6-PWM0{slash}RSS{slash}DIO10-Pad6)") (class "Default")
      (node (ref "U6") (pin "6") (pinfunction "PWM0/RSS/DIO10_6") (pintype "input+no_connect"))
    )
    (net (code "148") (name "unconnected-(U6-PWM1{slash}DIO11-Pad7)") (class "Default")
      (node (ref "U6") (pin "7") (pinfunction "PWM1/DIO11_7") (pintype "input+no_connect"))
    )
    (net (code "149") (name "unconnected-(U6-RST-Pad5)") (class "Default")
      (node (ref "U6") (pin "5") (pinfunction "RST_5") (pintype "input+no_connect"))
    )
    (net (code "150") (name "unconnected-(U6-VREF-Pad14)") (class "Default")
      (node (ref "U6") (pin "14") (pinfunction "VREF_14") (pintype "input+no_connect"))
    )
    (net (code "151") (name "unconnected-(U6-n_CTS{slash}DIO7-Pad12)") (class "Default")
      (node (ref "U6") (pin "12") (pinfunction "n_CTS/DIO7_12") (pintype "unspecified+no_connect"))
    )
    (net (code "152") (name "unconnected-(U6-n_DTR{slash}SLEEP_RQ{slash}DIO8-Pad9)") (class "Default")
      (node (ref "U6") (pin "9") (pinfunction "n_DTR/SLEEP_RQ/DIO8_9") (pintype "bidirectional+no_connect"))
    )
    (net (code "153") (name "unconnected-(U6-n_RTS{slash}DIO6-Pad16)") (class "Default")
      (node (ref "U6") (pin "16") (pinfunction "n_RTS/DIO6_16") (pintype "bidirectional+no_connect"))
    )
    (net (code "154") (name "unconnected-(U13-Vin+-Pad6)") (class "Default")
      (node (ref "U13") (pin "6") (pinfunction "Vin+_6") (pintype "input+no_connect"))
    )
    (net (code "155") (name "unconnected-(U13-Vin--Pad5)") (class "Default")
      (node (ref "U13") (pin "5") (pinfunction "Vin-_5") (pintype "input+no_connect"))
    )
    (net (code "156") (name "unconnected-(U35-3v3-Pad2)") (class "Default")
      (node (ref "U35") (pin "2") (pinfunction "3v3_2") (pintype "unspecified+no_connect"))
    )
    (net (code "157") (name "unconnected-(U35-BT-Pad12)") (class "Default")
      (node (ref "U35") (pin "12") (pinfunction "BT_12") (pintype "unspecified+no_connect"))
    )
    (net (code "158") (name "unconnected-(U35-CS-Pad7)") (class "Default")
      (node (ref "U35") (pin "7") (pinfunction "CS_7") (pintype "unspecified+no_connect"))
    )
    (net (code "159") (name "unconnected-(U35-DI-Pad8)") (class "Default")
      (node (ref "U35") (pin "8") (pinfunction "DI_8") (pintype "unspecified+no_connect"))
    )
    (net (code "160") (name "unconnected-(U35-INT-Pad6)") (class "Default")
      (node (ref "U35") (pin "6") (pinfunction "INT_6") (pintype "unspecified+no_connect"))
    )
    (net (code "161") (name "unconnected-(U35-P0-Pad11)") (class "Default")
      (node (ref "U35") (pin "11") (pinfunction "P0_11") (pintype "unspecified+no_connect"))
    )
    (net (code "162") (name "unconnected-(U35-P1-Pad10)") (class "Default")
      (node (ref "U35") (pin "10") (pinfunction "P1_10") (pintype "unspecified+no_connect"))
    )
    (net (code "163") (name "unconnected-(U35-RST-Pad9)") (class "Default")
      (node (ref "U35") (pin "9") (pinfunction "RST_9") (pintype "unspecified+no_connect"))
    )
  )
)
